# Hovedkort.net
KiCad netlist of a schematic drawn in Altium Designer
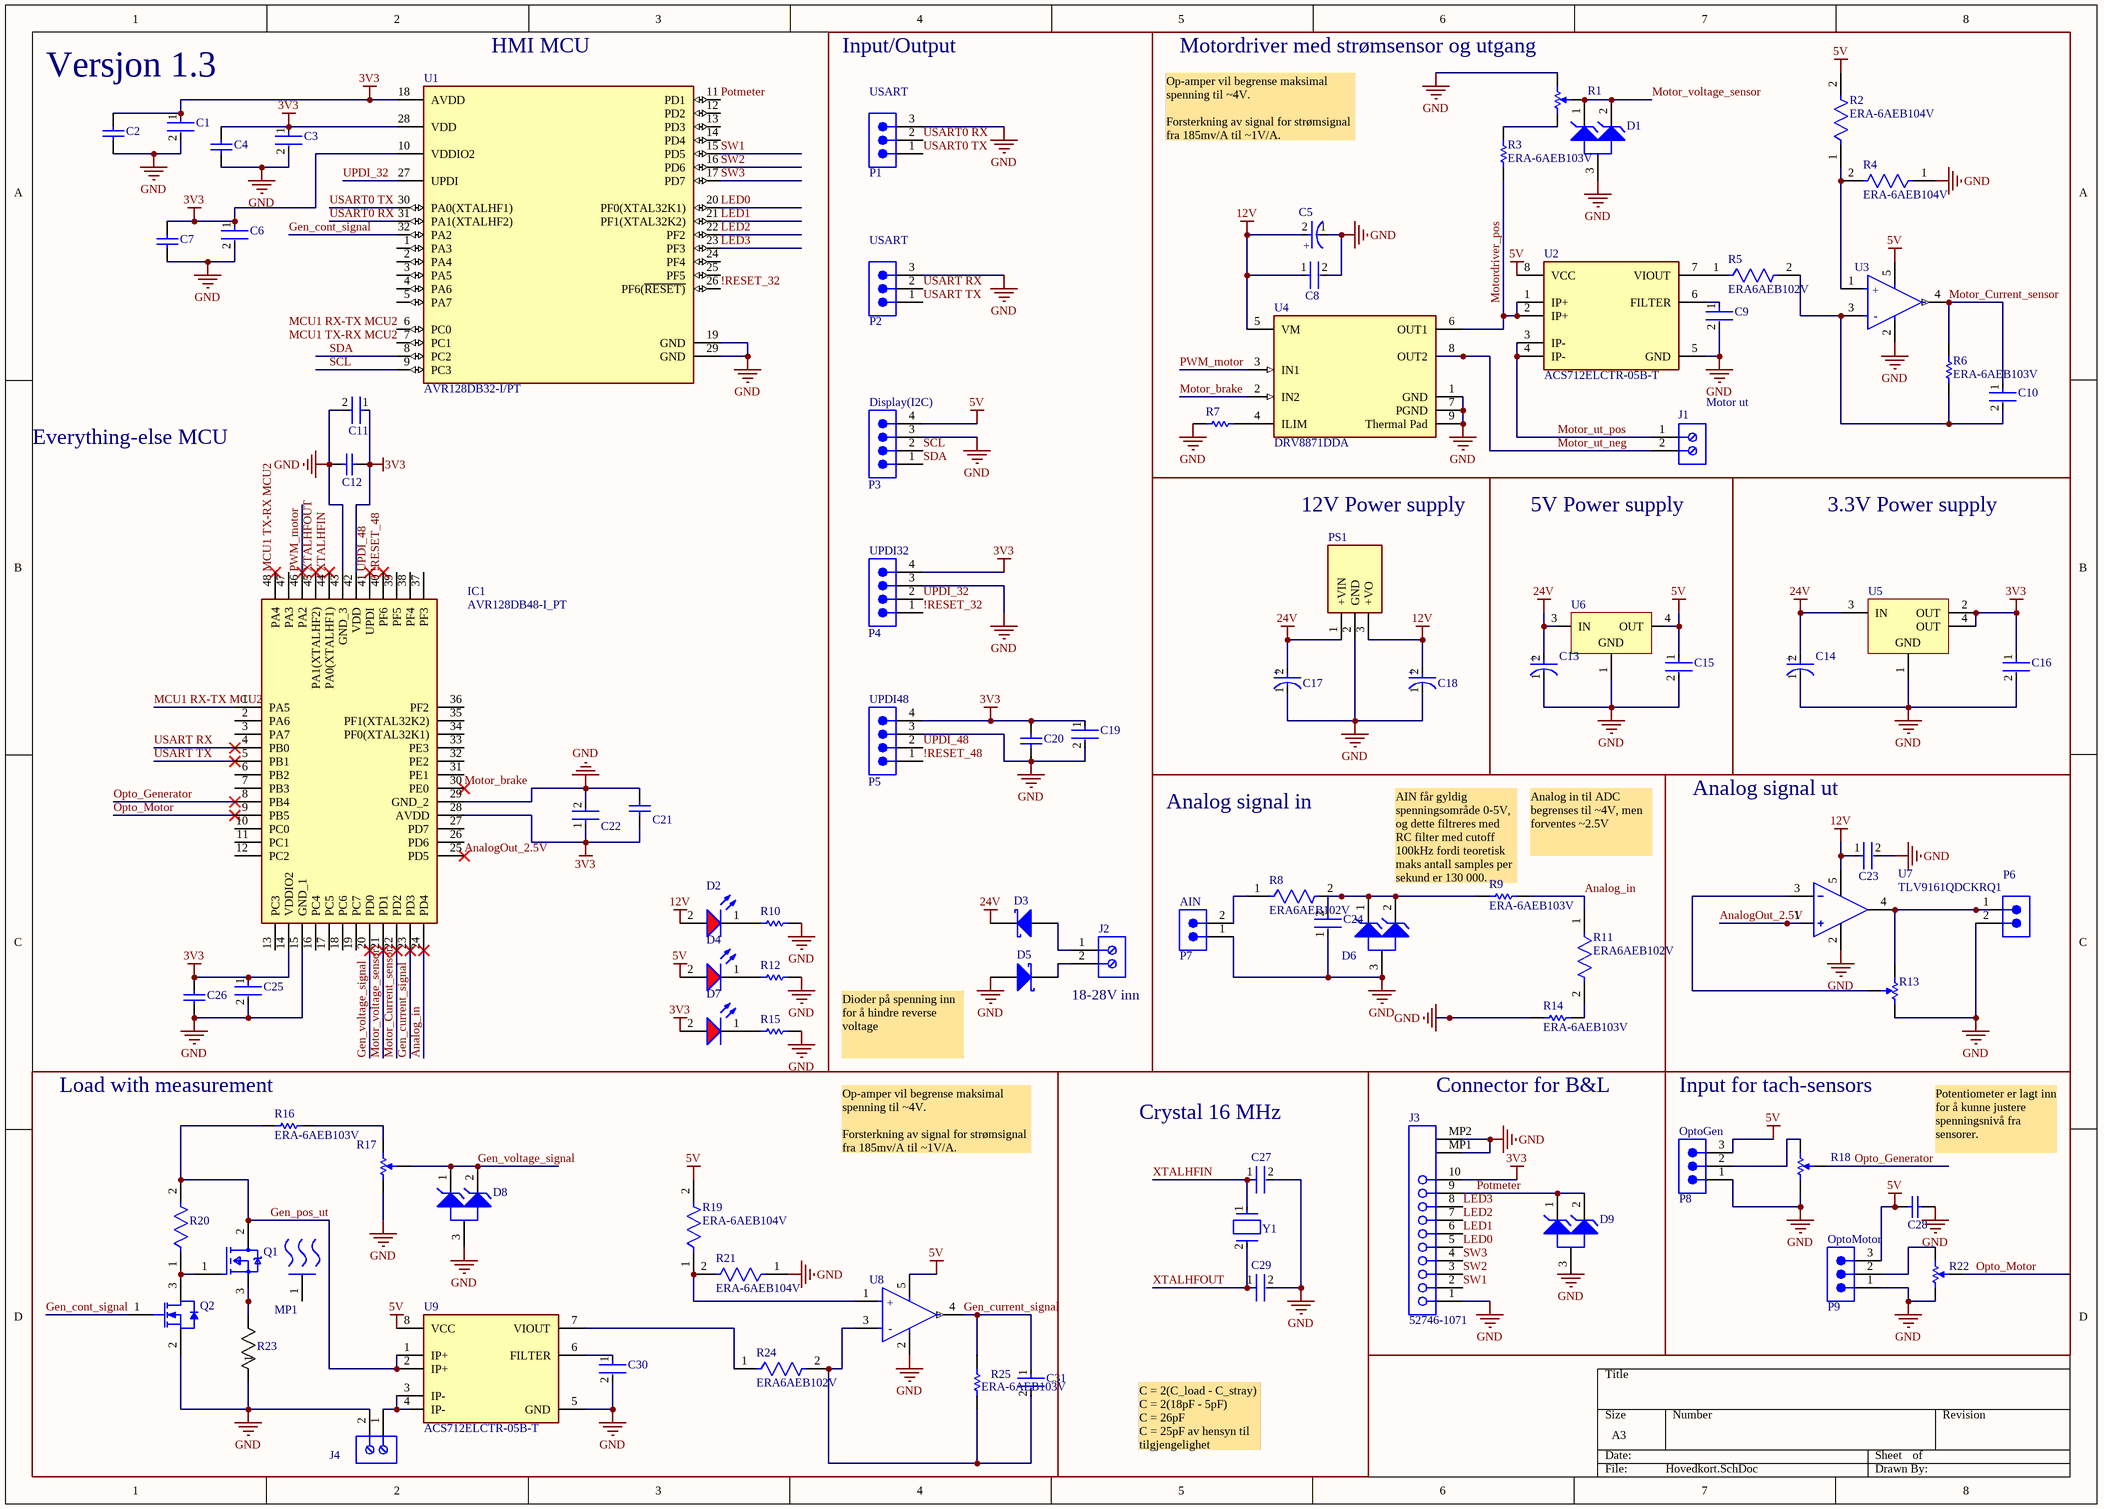
[diagram p0: Hovedkort.SchDoc]

(export (version "E")
  (design (tool "Eeschema 10.0.6"))
  (components
    (comp (ref "C1")
      (value "08055C104KAT2A")
      (footprint "FP-0805-L_2_01_0_2-W_1_25-IPC_C")
      (description "General Purpose Ceramic Capacitor, 0805, 100nF, 10%, X7R, 0.15, 50V")
      (fields (field (name "TOLERANCE") "10%") (field (name "VOLTAGE") "50V"))
      (libsource (lib "Altium Content Vault") (part "02cd4be3c70576c341d710602a673aa"))
    )
    (comp (ref "C2")
      (value "C0805C103K5RACTU")
      (footprint "CAPC2013X88X50LL20T25")
      (fields (field (name "MANUFACTURER") "Kemet"))
      (libsource (lib "Altium Content Vault") (part "CAP"))
    )
    (comp (ref "C3")
      (value "08055C104KAT2A")
      (footprint "FP-0805-L_2_01_0_2-W_1_25-IPC_C")
      (description "General Purpose Ceramic Capacitor, 0805, 100nF, 10%, X7R, 0.15, 50V")
      (fields (field (name "TOLERANCE") "10%") (field (name "VOLTAGE") "50V"))
      (libsource (lib "Altium Content Vault") (part "02cd4be3c70576c341d710602a673aa"))
    )
    (comp (ref "C4")
      (value "C0805C103K5RACTU")
      (footprint "CAPC2013X88X50LL20T25")
      (fields (field (name "MANUFACTURER") "Kemet"))
      (libsource (lib "Altium Content Vault") (part "CAP"))
    )
    (comp (ref "C5")
      (value "EEEFK1V220R")
      (footprint "FP-FKC-MFG")
      (description "CAP ALUM 22UF 20% 35V SMD")
      (fields (field (name "VOLTAGE") "35V") (field (name "TOLERANCE") "20%"))
      (libsource (lib "Altium Content Vault") (part "a00bbbee19879c290e62620ae7e47b1"))
    )
    (comp (ref "C6")
      (value "08055C104KAT2A")
      (footprint "FP-0805-L_2_01_0_2-W_1_25-IPC_C")
      (description "General Purpose Ceramic Capacitor, 0805, 100nF, 10%, X7R, 0.15, 50V")
      (fields (field (name "TOLERANCE") "10%") (field (name "VOLTAGE") "50V"))
      (libsource (lib "Altium Content Vault") (part "02cd4be3c70576c341d710602a673aa"))
    )
    (comp (ref "C7")
      (value "C0805C103K5RACTU")
      (footprint "CAPC2013X88X50LL20T25")
      (fields (field (name "MANUFACTURER") "Kemet"))
      (libsource (lib "Altium Content Vault") (part "CAP"))
    )
    (comp (ref "C8")
      (value "08055C104KAT2A")
      (footprint "FP-0805-L_2_01_0_2-W_1_25-IPC_C")
      (description "General Purpose Ceramic Capacitor, 0805, 100nF, 10%, X7R, 0.15, 50V")
      (fields (field (name "TOLERANCE") "10%") (field (name "VOLTAGE") "50V"))
      (libsource (lib "Altium Content Vault") (part "02cd4be3c70576c341d710602a673aa"))
    )
    (comp (ref "C9")
      (value "08055C104KAT2A")
      (footprint "FP-0805-L_2_01_0_2-W_1_25-IPC_C")
      (description "General Purpose Ceramic Capacitor, 0805, 100nF, 10%, X7R, 0.15, 50V")
      (fields (field (name "TOLERANCE") "10%") (field (name "VOLTAGE") "50V"))
      (libsource (lib "Altium Content Vault") (part "02cd4be3c70576c341d710602a673aa"))
    )
    (comp (ref "C10")
      (value "C0805C102J1GACTU")
      (footprint "FP-C0805C-DN-MFG")
      (description "CAP CER 1000PF 100V C0G/NP0 0805")
      (fields (field (name "MANUFACTURER") "KEMET") (field (name "TOLERANCE") "0.05"))
      (libsource (lib "Altium Content Vault") (part "b4654b650e69147ec39a6b967a45e02"))
    )
    (comp (ref "C11")
      (value "08055C104KAT2A")
      (footprint "FP-0805-L_2_01_0_2-W_1_25-IPC_C")
      (description "General Purpose Ceramic Capacitor, 0805, 100nF, 10%, X7R, 0.15, 50V")
      (fields (field (name "TOLERANCE") "10%") (field (name "VOLTAGE") "50V"))
      (libsource (lib "Altium Content Vault") (part "02cd4be3c70576c341d710602a673aa"))
    )
    (comp (ref "C12")
      (value "C0805C103K5RACTU")
      (footprint "CAPC2013X88X50LL20T25")
      (fields (field (name "MANUFACTURER") "Kemet"))
      (libsource (lib "Altium Content Vault") (part "CAP"))
    )
    (comp (ref "C13")
      (value "EEE-FK1H100UR")
      (footprint "FP-FKC-MFG")
      (description "CAP ALUM 10UF 20% 50V SMD")
      (fields (field (name "TOLERANCE") "20%") (field (name "VOLTAGE") "50V"))
      (libsource (lib "Altium Content Vault") (part "a00bbbee19879c290e62620ae7e47b1"))
    )
    (comp (ref "C14")
      (value "EEE-FK1H100UR")
      (footprint "FP-FKC-MFG")
      (description "CAP ALUM 10UF 20% 50V SMD")
      (fields (field (name "TOLERANCE") "20%") (field (name "VOLTAGE") "50V"))
      (libsource (lib "Altium Content Vault") (part "a00bbbee19879c290e62620ae7e47b1"))
    )
    (comp (ref "C15")
      (value "C0805C106K8PACTU")
      (footprint "FP-C0805C-DG-MFG")
      (description "CAP CER 10UF 10V X5R 0805")
      (fields (field (name "TOLERANCE") "10%") (field (name "MANUFACTURER") "Kemet"))
      (libsource (lib "Altium Content Vault") (part "11868f565c42a9108669ba33697ecf6"))
    )
    (comp (ref "C16")
      (value "C0805C106K8PACTU")
      (footprint "FP-C0805C-DG-MFG")
      (description "CAP CER 10UF 10V X5R 0805")
      (fields (field (name "TOLERANCE") "10%") (field (name "MANUFACTURER") "Kemet"))
      (libsource (lib "Altium Content Vault") (part "11868f565c42a9108669ba33697ecf6"))
    )
    (comp (ref "C17")
      (value "EEEFK1V220R")
      (footprint "FP-FKC-MFG")
      (description "CAP ALUM 22UF 20% 35V SMD")
      (fields (field (name "VOLTAGE") "35V") (field (name "TOLERANCE") "20%"))
      (libsource (lib "Altium Content Vault") (part "a00bbbee19879c290e62620ae7e47b1"))
    )
    (comp (ref "C18")
      (value "EEEFK1V220R")
      (footprint "FP-FKC-MFG")
      (description "CAP ALUM 22UF 20% 35V SMD")
      (fields (field (name "VOLTAGE") "35V") (field (name "TOLERANCE") "20%"))
      (libsource (lib "Altium Content Vault") (part "a00bbbee19879c290e62620ae7e47b1"))
    )
    (comp (ref "C19")
      (value "08055C104KAT2A")
      (footprint "FP-0805-L_2_01_0_2-W_1_25-IPC_C")
      (description "General Purpose Ceramic Capacitor, 0805, 100nF, 10%, X7R, 0.15, 50V")
      (fields (field (name "TOLERANCE") "10%") (field (name "VOLTAGE") "50V"))
      (libsource (lib "Altium Content Vault") (part "02cd4be3c70576c341d710602a673aa"))
    )
    (comp (ref "C20")
      (value "C0805C103K5RACTU")
      (footprint "CAPC2013X88X50LL20T25")
      (fields (field (name "MANUFACTURER") "Kemet"))
      (libsource (lib "Altium Content Vault") (part "CAP"))
    )
    (comp (ref "C21")
      (value "C0805C103K5RACTU")
      (footprint "CAPC2013X88X50LL20T25")
      (fields (field (name "MANUFACTURER") "Kemet"))
      (libsource (lib "Altium Content Vault") (part "CAP"))
    )
    (comp (ref "C22")
      (value "08055C104KAT2A")
      (footprint "FP-0805-L_2_01_0_2-W_1_25-IPC_C")
      (description "General Purpose Ceramic Capacitor, 0805, 100nF, 10%, X7R, 0.15, 50V")
      (fields (field (name "TOLERANCE") "10%") (field (name "VOLTAGE") "50V"))
      (libsource (lib "Altium Content Vault") (part "02cd4be3c70576c341d710602a673aa"))
    )
    (comp (ref "C23")
      (value "08055C104KAT2A")
      (footprint "FP-0805-L_2_01_0_2-W_1_25-IPC_C")
      (description "General Purpose Ceramic Capacitor, 0805, 100nF, 10%, X7R, 0.15, 50V")
      (fields (field (name "TOLERANCE") "10%") (field (name "VOLTAGE") "50V"))
      (libsource (lib "Altium Content Vault") (part "02cd4be3c70576c341d710602a673aa"))
    )
    (comp (ref "C24")
      (value "GRM2165C2A162JA01D")
      (footprint "FP-GRM216-0_1-IPC_A")
      (description "Chip Multilayer Ceramic Capacitors for General Purpose, 0805, 1600pF, C0G, 30ppm/°C, 5%, 100V")
      (fields (field (name "TOLERANCE") "5%"))
      (libsource (lib "Altium Content Vault") (part "236180d848d6139a670b325ea6854c9"))
    )
    (comp (ref "C25")
      (value "08055C104KAT2A")
      (footprint "FP-0805-L_2_01_0_2-W_1_25-IPC_C")
      (description "General Purpose Ceramic Capacitor, 0805, 100nF, 10%, X7R, 0.15, 50V")
      (fields (field (name "TOLERANCE") "10%") (field (name "VOLTAGE") "50V"))
      (libsource (lib "Altium Content Vault") (part "02cd4be3c70576c341d710602a673aa"))
    )
    (comp (ref "C26")
      (value "C0805C103K5RACTU")
      (footprint "CAPC2013X88X50LL20T25")
      (fields (field (name "MANUFACTURER") "Kemet"))
      (libsource (lib "Altium Content Vault") (part "CAP"))
    )
    (comp (ref "C27")
      (value "C0805C103J3GACTU")
      (footprint "FP-C0805C-DN-MFG")
      (description "CAP CER 10000PF 25V 5% NP0 0805")
      (fields
        (field (name "OCTOPART") "https://octopart.com/c0805c103j3gactu-kemet-12563663")
        (field (name "TOLERANCE") "0.05")
      )
      (libsource (lib "Altium Content Vault") (part "b4654b650e69147ec39a6b967a45e02"))
    )
    (comp (ref "C28")
      (value "C0805C103K5RACTU")
      (footprint "CAPC2013X88X50LL20T25")
      (fields (field (name "MANUFACTURER") "Kemet"))
      (libsource (lib "Altium Content Vault") (part "CAP"))
    )
    (comp (ref "C29")
      (value "C0805C103J3GACTU")
      (footprint "FP-C0805C-DN-MFG")
      (description "CAP CER 10000PF 25V 5% NP0 0805")
      (fields
        (field (name "OCTOPART") "https://octopart.com/c0805c103j3gactu-kemet-12563663")
        (field (name "TOLERANCE") "0.05")
      )
      (libsource (lib "Altium Content Vault") (part "b4654b650e69147ec39a6b967a45e02"))
    )
    (comp (ref "C30")
      (value "08055C104KAT2A")
      (footprint "FP-0805-L_2_01_0_2-W_1_25-IPC_C")
      (description "General Purpose Ceramic Capacitor, 0805, 100nF, 10%, X7R, 0.15, 50V")
      (fields (field (name "TOLERANCE") "10%") (field (name "VOLTAGE") "50V"))
      (libsource (lib "Altium Content Vault") (part "02cd4be3c70576c341d710602a673aa"))
    )
    (comp (ref "C31")
      (value "C0805C102J1GACTU")
      (footprint "FP-C0805C-DN-MFG")
      (description "CAP CER 1000PF 100V C0G/NP0 0805")
      (fields (field (name "MANUFACTURER") "KEMET") (field (name "TOLERANCE") "0.05"))
      (libsource (lib "Altium Content Vault") (part "b4654b650e69147ec39a6b967a45e02"))
    )
    (comp (ref "D1")
      (value "MMBZ6V2ALT1G")
      (footprint "ONSC-SOT-23-3-318-08_V")
      (fields (field (name "MANUFACTURER") "On Semiconductor"))
      (libsource (lib "Altium Content Vault") (part "ONSC-K1K2A3-3"))
    )
    (comp (ref "D2")
      (value "150080SS75000")
      (footprint "WL-SMCW_0805_150080xx75000")
      (libsource (lib "Altium Content Vault") (part "LED_Red_2A-1K"))
    )
    (comp (ref "D3")
      (value "STPS2H100A")
      (footprint "STM-SMA-2_V")
      (description "Power Schottky Rectifier, 2 A, 100 V, 2-Pin SMD (SMA), RoHS, Tape and Reel")
      (fields (field (name "MANUFACTURER") "STMicroelectronics"))
      (libsource (lib "Altium Content Vault") (part "DSKY-AK-2"))
    )
    (comp (ref "D4")
      (value "150080SS75000")
      (footprint "WL-SMCW_0805_150080xx75000")
      (libsource (lib "Altium Content Vault") (part "LED_Red_2A-1K"))
    )
    (comp (ref "D5")
      (value "STPS2H100A")
      (footprint "STM-SMA-2_V")
      (description "Power Schottky Rectifier, 2 A, 100 V, 2-Pin SMD (SMA), RoHS, Tape and Reel")
      (fields (field (name "MANUFACTURER") "STMicroelectronics"))
      (libsource (lib "Altium Content Vault") (part "DSKY-AK-2"))
    )
    (comp (ref "D6")
      (value "ESD7L5.0DT5G")
      (footprint "ONSC-SOT-723-3-631AA-01_V")
      (fields (field (name "MANUFACTURER") "On Semiconductor"))
      (libsource (lib "Altium Content Vault") (part "ONSC-K1K2A3-3"))
    )
    (comp (ref "D7")
      (value "150080SS75000")
      (footprint "WL-SMCW_0805_150080xx75000")
      (libsource (lib "Altium Content Vault") (part "LED_Red_2A-1K"))
    )
    (comp (ref "D8")
      (value "MMBZ6V2ALT1G")
      (footprint "ONSC-SOT-23-3-318-08_V")
      (fields (field (name "MANUFACTURER") "On Semiconductor"))
      (libsource (lib "Altium Content Vault") (part "ONSC-K1K2A3-3"))
    )
    (comp (ref "D9")
      (value "SZMMBZ27VAWT1G")
      (footprint "ONSC-SC-70-3-419-04_V")
      (fields (field (name "MANUFACTURER") "On Semiconductor"))
      (libsource (lib "Altium Content Vault") (part "ONSC-K1K2A3-3"))
    )
    (comp (ref "IC1")
      (value "AVR128DB48-I_PT")
      (footprint "QFP50P900X900X120-48N")
      (description "Integrated Circuit")
      (fields
        (field (name "MANUFACTURER_PART_NUMBER") "AVR128DB48-I/PT")
        (field (name "MOUSER PART NUMBER") "579-AVR128DB48-I/PT")
      )
      (libsource (lib "AVR128DB48-iPTv3") (part "AVR128DB48-I_PT"))
    )
    (comp (ref "J1")
      (value "691103110002")
      (footprint "691103110002")
      (fields (field (name "VOLTAGE") "125V"))
      (libsource (lib "Altium Content Vault") (part "TBL - 1R - 02P - Screw"))
    )
    (comp (ref "J2")
      (value "691103110002")
      (footprint "691103110002")
      (fields (field (name "VOLTAGE") "125V"))
      (libsource (lib "Altium Content Vault") (part "TBL - 1R - 02P - Screw"))
    )
    (comp (ref "J3")
      (value "52746-1071")
      (footprint "MOLX-52746-1071")
      (fields (field (name "MANUFACTURER") "Molex"))
      (libsource (lib "Altium Content Vault") (part "MOLX-52746-1071"))
    )
    (comp (ref "J4")
      (value "691103110002")
      (footprint "691103110002")
      (fields (field (name "VOLTAGE") "125V"))
      (libsource (lib "Altium Content Vault") (part "TBL - 1R - 02P - Screw"))
    )
    (comp (ref "MP1")
      (value "FA-T220-25E")
      (footprint "FP-FA-T220-25E-MFG")
      (description "HEATSINK TO-218,TO-220,TO-247")
      (libsource (lib "Altium Content Vault") (part "6f3fc7de95079af55ca25afa00d65c5"))
    )
    (comp (ref "P1")
      (value "61300311121")
      (footprint "61300311121")
      (libsource (lib "Altium Content Vault") (part "Header_Male_1R_03P"))
    )
    (comp (ref "P2")
      (value "61300311121")
      (footprint "61300311121")
      (libsource (lib "Altium Content Vault") (part "Header_Male_1R_03P"))
    )
    (comp (ref "P3")
      (value "61300411121")
      (footprint "61300411121")
      (libsource (lib "Altium Content Vault") (part "Header_Male_1R_04P"))
    )
    (comp (ref "P4")
      (value "61300411121")
      (footprint "61300411121")
      (libsource (lib "Altium Content Vault") (part "Header_Male_1R_04P"))
    )
    (comp (ref "P5")
      (value "61300411121")
      (footprint "61300411121")
      (libsource (lib "Altium Content Vault") (part "Header_Male_1R_04P"))
    )
    (comp (ref "P6")
      (value "61300211121")
      (footprint "61300211121")
      (libsource (lib "Altium Content Vault") (part "Header_Male_1R_02P"))
    )
    (comp (ref "P7")
      (value "61300211121")
      (footprint "61300211121")
      (libsource (lib "Altium Content Vault") (part "Header_Male_1R_02P"))
    )
    (comp (ref "P8")
      (value "61300311121")
      (footprint "61300311121")
      (libsource (lib "Altium Content Vault") (part "Header_Male_1R_03P"))
    )
    (comp (ref "P9")
      (value "61300311121")
      (footprint "61300311121")
      (libsource (lib "Altium Content Vault") (part "Header_Male_1R_03P"))
    )
    (comp (ref "PS1")
      (value "P7812-2000R-S")
      (footprint "P78032000RS")
      (description "Power Supply")
      (libsource (lib "P7803-2000R-S") (part "P7803-2000R-S"))
    )
    (comp (ref "Q1")
      (value "IRFZ44VPBF")
      (footprint "FP-PG-TO220-3-MFG")
      (description "MOSFET N-CH 60V 55A TO220AB")
      (libsource (lib "Altium Content Vault") (part "8b62d417cbef8344eebe0bde0c45977"))
    )
    (comp (ref "Q2")
      (value "BSH103,215")
      (footprint "NXP-SOT23_N")
      (description "N-Channel Enhancement Mode MOS Transistor, 30 V, 0.85 A, 3-Pin SOT23, Tape and Reel")
      (fields (field (name "MANUFACTURER") "NXP Semiconductors"))
      (libsource (lib "Altium Content Vault") (part "NXP-NMOS-GSD-3_B"))
    )
    (comp (ref "R1")
      (value "TC33X-2-103E")
      (footprint "BOUR-TC33X-2_V")
      (description "Trimming Potentiometer, 10000 Ohm, -40 to 100 degC, 3-Pin SMD, RoHS, Tape and Reel")
      (fields (field (name "TOLERANCE") "25%") (field (name "MANUFACTURER") "Bourns"))
      (libsource (lib "Altium Content Vault") (part "RES-ADJ-3_A"))
    )
    (comp (ref "R2")
      (value "ERA-6AEB104V")
      (footprint "FP-ERA6A-IPC_B")
      (description "RES 100K OHM 0.1% 1/8W 0805")
      (fields (field (name "TOLERANCE") "0.1%"))
      (libsource (lib "Altium Content Vault") (part "1029c3af85768c4190bb7ad29bc67b5"))
    )
    (comp (ref "R3")
      (value "ERA-6AEB103V")
      (footprint "RESC2013X60X40LL20T25_A")
      (fields (field (name "TOLERANCE") "0.1%") (field (name "MANUFACTURER") "Panasonic"))
      (libsource (lib "Altium Content Vault") (part "RES-2"))
    )
    (comp (ref "R4")
      (value "ERA-6AEB104V")
      (footprint "FP-ERA6A-IPC_B")
      (description "RES 100K OHM 0.1% 1/8W 0805")
      (fields (field (name "TOLERANCE") "0.1%"))
      (libsource (lib "Altium Content Vault") (part "1029c3af85768c4190bb7ad29bc67b5"))
    )
    (comp (ref "R5")
      (value "ERA6AEB102V")
      (footprint "FP-ERA6A-IPC_C")
      (description "RES 1K OHM 0.1% 1/8W 0805")
      (fields (field (name "TOLERANCE") "0.1%"))
      (libsource (lib "Altium Content Vault") (part "1029c3af85768c4190bb7ad29bc67b5"))
    )
    (comp (ref "R6")
      (value "ERA-6AEB103V")
      (footprint "RESC2013X60X40LL20T25_A")
      (fields (field (name "TOLERANCE") "0.1%") (field (name "MANUFACTURER") "Panasonic"))
      (libsource (lib "Altium Content Vault") (part "RES-2"))
    )
    (comp (ref "R7")
      (value "ERJ-6GEYJ303V")
      (footprint "RESC2013X70X40NL20T20")
      (fields (field (name "MANUFACTURER") "Panasonic"))
      (libsource (lib "Altium Content Vault") (part "RES"))
    )
    (comp (ref "R8")
      (value "ERA6AEB102V")
      (footprint "FP-ERA6A-IPC_C")
      (description "RES 1K OHM 0.1% 1/8W 0805")
      (fields (field (name "TOLERANCE") "0.1%"))
      (libsource (lib "Altium Content Vault") (part "1029c3af85768c4190bb7ad29bc67b5"))
    )
    (comp (ref "R9")
      (value "ERA-6AEB103V")
      (footprint "RESC2013X60X40LL20T25_A")
      (fields (field (name "TOLERANCE") "0.1%") (field (name "MANUFACTURER") "Panasonic"))
      (libsource (lib "Altium Content Vault") (part "RES-2"))
    )
    (comp (ref "R10")
      (value "ERJ-6GEYJ511V")
      (footprint "RESC2013X70X40ML20T20")
      (fields (field (name "MANUFACTURER") "Panasonic"))
      (libsource (lib "Altium Content Vault") (part "RES"))
    )
    (comp (ref "R11")
      (value "ERA6AEB102V")
      (footprint "FP-ERA6A-IPC_C")
      (description "RES 1K OHM 0.1% 1/8W 0805")
      (fields (field (name "TOLERANCE") "0.1%"))
      (libsource (lib "Altium Content Vault") (part "1029c3af85768c4190bb7ad29bc67b5"))
    )
    (comp (ref "R12")
      (value "ERA6AEB1400V")
      (footprint "RESC2013X60X40NL20T25")
      (fields (field (name "MANUFACTURER") "Panasonic"))
      (libsource (lib "Altium Content Vault") (part "RES"))
    )
    (comp (ref "R13")
      (value "TC33X-2-103E")
      (footprint "BOUR-TC33X-2_V")
      (description "Trimming Potentiometer, 10000 Ohm, -40 to 100 degC, 3-Pin SMD, RoHS, Tape and Reel")
      (fields (field (name "TOLERANCE") "25%") (field (name "MANUFACTURER") "Bourns"))
      (libsource (lib "Altium Content Vault") (part "RES-ADJ-3_A"))
    )
    (comp (ref "R14")
      (value "ERA-6AEB103V")
      (footprint "RESC2013X60X40LL20T25_A")
      (fields (field (name "TOLERANCE") "0.1%") (field (name "MANUFACTURER") "Panasonic"))
      (libsource (lib "Altium Content Vault") (part "RES-2"))
    )
    (comp (ref "R15")
      (value "ERJ6ENF56R0V")
      (footprint "RESC2013X70X40NL20T20")
      (fields (field (name "MANUFACTURER") "Panasonic"))
      (libsource (lib "Altium Content Vault") (part "RES"))
    )
    (comp (ref "R16")
      (value "ERA-6AEB103V")
      (footprint "RESC2013X60X40LL20T25_A")
      (fields (field (name "TOLERANCE") "0.1%") (field (name "MANUFACTURER") "Panasonic"))
      (libsource (lib "Altium Content Vault") (part "RES-2"))
    )
    (comp (ref "R17")
      (value "TC33X-2-103E")
      (footprint "BOUR-TC33X-2_V")
      (description "Trimming Potentiometer, 10000 Ohm, -40 to 100 degC, 3-Pin SMD, RoHS, Tape and Reel")
      (fields (field (name "TOLERANCE") "25%") (field (name "MANUFACTURER") "Bourns"))
      (libsource (lib "") (part "RES-ADJ-3_A_1"))
    )
    (comp (ref "R18")
      (value "TC33X-2-103E")
      (footprint "BOUR-TC33X-2_V")
      (description "Trimming Potentiometer, 10000 Ohm, -40 to 100 degC, 3-Pin SMD, RoHS, Tape and Reel")
      (fields (field (name "TOLERANCE") "25%") (field (name "MANUFACTURER") "Bourns"))
      (libsource (lib "Altium Content Vault") (part "RES-ADJ-3_A"))
    )
    (comp (ref "R19")
      (value "ERA-6AEB104V")
      (footprint "FP-ERA6A-IPC_B")
      (description "RES 100K OHM 0.1% 1/8W 0805")
      (fields (field (name "TOLERANCE") "0.1%"))
      (libsource (lib "Altium Content Vault") (part "1029c3af85768c4190bb7ad29bc67b5"))
    )
    (comp (ref "R20")
      (value "CRCW080510K0FKEA")
      (footprint "FP-CRCW0805-e3-IPC_A")
      (description "RES Thick Film, 10kΩ, 1%, 0.125W, 100ppm/°C, 0805")
      (fields (field (name "TOLERANCE") "1%"))
      (libsource (lib "Altium Content Vault") (part "1029c3af85768c4190bb7ad29bc67b5"))
    )
    (comp (ref "R21")
      (value "ERA-6AEB104V")
      (footprint "FP-ERA6A-IPC_B")
      (description "RES 100K OHM 0.1% 1/8W 0805")
      (fields (field (name "TOLERANCE") "0.1%"))
      (libsource (lib "Altium Content Vault") (part "1029c3af85768c4190bb7ad29bc67b5"))
    )
    (comp (ref "R22")
      (value "TC33X-2-103E")
      (footprint "BOUR-TC33X-2_V")
      (description "Trimming Potentiometer, 10000 Ohm, -40 to 100 degC, 3-Pin SMD, RoHS, Tape and Reel")
      (fields (field (name "TOLERANCE") "25%") (field (name "MANUFACTURER") "Bourns"))
      (libsource (lib "Altium Content Vault") (part "RES-ADJ-3_A"))
    )
    (comp (ref "R23")
      (value "AC05000001008JAC00")
      (footprint "RES_AC05_VIS")
      (fields (field (name "TOLERANCE") "5%"))
      (libsource (lib "Altium Content Vault") (part "AC05000001008JAC00"))
    )
    (comp (ref "R24")
      (value "ERA6AEB102V")
      (footprint "FP-ERA6A-IPC_C")
      (description "RES 1K OHM 0.1% 1/8W 0805")
      (fields (field (name "TOLERANCE") "0.1%"))
      (libsource (lib "Altium Content Vault") (part "1029c3af85768c4190bb7ad29bc67b5"))
    )
    (comp (ref "R25")
      (value "ERA-6AEB103V")
      (footprint "RESC2013X60X40LL20T25_A")
      (fields (field (name "TOLERANCE") "0.1%") (field (name "MANUFACTURER") "Panasonic"))
      (libsource (lib "Altium Content Vault") (part "RES-2"))
    )
    (comp (ref "U1")
      (value "AVR128DB32-I/PT")
      (footprint "FP-C04-074-PT-MFG")
      (description "AVR128DB32-I/PT 8-bit AVR MCU, 128 KB, 16384 Bytes, 24 MHz, 1.8 to 5.5V, TQFP-32, RoHS")
      (libsource (lib "Altium Content Vault") (part "862fc9fb584fc62f03dcc95c93de750"))
    )
    (comp (ref "U2")
      (value "ACS712ELCTR-05B-T")
      (footprint "FP-LC-8-IPC_A")
      (description "SENSOR CURRENT HALL 5A AC/DC")
      (fields (field (name "VOLTAGE") "5V"))
      (libsource (lib "Altium Content Vault") (part "160a4736de78720bdb7fdad13a6f0ac"))
    )
    (comp (ref "U3")
      (value "LM321LVIDCKR")
      (footprint "FP-DCK0005A-IPC_B")
      (description "IC OPAMP GP 1 CIRCUIT SC70-5")
      (libsource (lib "Altium Content Vault") (part "471d8b929410cd356ad4b122f572ce5"))
    )
    (comp (ref "U4")
      (value "DRV8871DDA")
      (footprint "FP-DDA0008E-IPC_B")
      (description "IC MOTOR DRVR UNIPLR 8SO PWRPAD")
      (libsource (lib "Altium Content Vault") (part "e376993584eeff15c1aa71204cd03ad"))
    )
    (comp (ref "U5")
      (value "LD1086D2M33TR")
      (footprint "D2PAK_A_L")
      (description "1.5A, Low Drop Positive Voltage Regulator, 3.3V, 4-Pin D2PAK/A, Tape and Reel")
      (libsource (lib "Altium Content Vault") (part "PM-REG-LD1085-SOT4"))
    )
    (comp (ref "U6")
      (value "LD1086D2T50TR")
      (footprint "TO-263_N")
      (description "1.5A, Low Drop Positive Voltage Regulator, 5.0V, 3-Pin D2PAK, Tape and Reel")
      (libsource (lib "Altium Content Vault") (part "PM-REG-LD1085-SOT3"))
    )
    (comp (ref "U7")
      (value "TLV9161QDCKRQ1")
      (footprint "FP-DCK0005A-MFG")
      (libsource (lib "Altium Content Vault") (part "bd543cf93bb0a89a308ea7e9b7b5175"))
    )
    (comp (ref "U8")
      (value "LM321LVIDCKR")
      (footprint "FP-DCK0005A-IPC_B")
      (description "IC OPAMP GP 1 CIRCUIT SC70-5")
      (libsource (lib "Altium Content Vault") (part "471d8b929410cd356ad4b122f572ce5"))
    )
    (comp (ref "U9")
      (value "ACS712ELCTR-05B-T")
      (footprint "FP-LC-8-IPC_A")
      (description "SENSOR CURRENT HALL 5A AC/DC")
      (fields (field (name "VOLTAGE") "5V"))
      (libsource (lib "Altium Content Vault") (part "160a4736de78720bdb7fdad13a6f0ac"))
    )
    (comp (ref "Y1")
      (value "ABM3-16.000MHZ-B2-T")
      (footprint "FP-ABM3-MFG")
      (description "Crystal 16MHz ±20ppm 18pF SMD-2 5mm x 3.2mm")
      (fields (field (name "TOLERANCE") "20ppm"))
      (libsource (lib "Altium Content Vault") (part "c23a69dc6c9e2f18f2079038eb95dd1"))
    )
  )
  (nets
    (net (code "1") (name "/!RESET_32") (class "Default")
      (node (ref "P4") (pin "1") (pinfunction "1_1") (pintype "passive"))
      (node (ref "U1") (pin "26") (pinfunction "PF6(~{RESET)}_26") (pintype "bidirectional"))
    )
    (net (code "2") (name "/!RESET_48") (class "Default")
      (node (ref "IC1") (pin "40") (pinfunction "PF6_40") (pintype "passive"))
      (node (ref "P5") (pin "1") (pinfunction "1_1") (pintype "passive"))
    )
    (net (code "3") (name "/AnalogOut_2.5V") (class "Default")
      (node (ref "IC1") (pin "25") (pinfunction "PD5_25") (pintype "passive"))
      (node (ref "U7") (pin "1") (pinfunction "IN+_1") (pintype "tri_state"))
    )
    (net (code "4") (name "/Analog_in") (class "Default")
      (node (ref "IC1") (pin "24") (pinfunction "PD4_24") (pintype "passive"))
      (node (ref "R11") (pin "1") (pinfunction "1_1") (pintype "passive"))
      (node (ref "R9") (pin "1") (pinfunction "1_1") (pintype "passive"))
    )
    (net (code "5") (name "/Gen_cont_signal") (class "Default")
      (node (ref "Q2") (pin "1") (pinfunction "G_1") (pintype "passive"))
      (node (ref "U1") (pin "32") (pinfunction "PA2_32") (pintype "bidirectional"))
    )
    (net (code "6") (name "/Gen_current_signal") (class "Default")
      (node (ref "C31") (pin "1") (pinfunction "1_1") (pintype "passive"))
      (node (ref "IC1") (pin "23") (pinfunction "PD3_23") (pintype "passive"))
      (node (ref "R25") (pin "2") (pinfunction "2_2") (pintype "passive"))
      (node (ref "U8") (pin "4") (pinfunction "OUT_4") (pintype "output"))
    )
    (net (code "7") (name "/Gen_pos_ut") (class "Default")
      (node (ref "Q1") (pin "2") (pinfunction "DRAIN_2") (pintype "passive"))
      (node (ref "R16") (pin "2") (pinfunction "2_2") (pintype "passive"))
      (node (ref "R20") (pin "2") (pinfunction "2_2") (pintype "passive"))
      (node (ref "U9") (pin "1") (pinfunction "IP+_1") (pintype "passive"))
      (node (ref "U9") (pin "2") (pinfunction "IP+_2") (pintype "passive"))
    )
    (net (code "8") (name "/Gen_voltage_signal") (class "Default")
      (node (ref "D8") (pin "1") (pinfunction "K1_1") (pintype "passive"))
      (node (ref "D8") (pin "2") (pinfunction "K2_2") (pintype "passive"))
      (node (ref "IC1") (pin "20") (pinfunction "PD0_20") (pintype "passive"))
      (node (ref "R17") (pin "2") (pinfunction "2_2") (pintype "passive"))
    )
    (net (code "9") (name "/LED0") (class "Default")
      (node (ref "J3") (pin "5") (pinfunction "5_5") (pintype "passive"))
      (node (ref "U1") (pin "20") (pinfunction "PF0(XTAL32K1)_20") (pintype "bidirectional"))
    )
    (net (code "10") (name "/LED1") (class "Default")
      (node (ref "J3") (pin "6") (pinfunction "6_6") (pintype "passive"))
      (node (ref "U1") (pin "21") (pinfunction "PF1(XTAL32K2)_21") (pintype "bidirectional"))
    )
    (net (code "11") (name "/LED2") (class "Default")
      (node (ref "J3") (pin "7") (pinfunction "7_7") (pintype "passive"))
      (node (ref "U1") (pin "22") (pinfunction "PF2_22") (pintype "bidirectional"))
    )
    (net (code "12") (name "/LED3") (class "Default")
      (node (ref "J3") (pin "8") (pinfunction "8_8") (pintype "passive"))
      (node (ref "U1") (pin "23") (pinfunction "PF3_23") (pintype "bidirectional"))
    )
    (net (code "13") (name "/MCU1 RX-TX MCU2") (class "Default")
      (node (ref "IC1") (pin "1") (pinfunction "PA5_1") (pintype "passive"))
    )
    (net (code "14") (name "/MCU1 TX-RX MCU2") (class "Default")
      (node (ref "IC1") (pin "48") (pinfunction "PA4_48") (pintype "passive+no_connect"))
    )
    (net (code "15") (name "/Motor_Current_sensor") (class "Default")
      (node (ref "C10") (pin "1") (pinfunction "1_1") (pintype "passive"))
      (node (ref "IC1") (pin "22") (pinfunction "PD2_22") (pintype "passive"))
      (node (ref "R6") (pin "2") (pinfunction "2_2") (pintype "passive"))
      (node (ref "U3") (pin "4") (pinfunction "OUT_4") (pintype "output"))
    )
    (net (code "16") (name "/Motor_brake") (class "Default")
      (node (ref "IC1") (pin "30") (pinfunction "PE0_30") (pintype "passive"))
      (node (ref "U4") (pin "2") (pinfunction "IN2_2") (pintype "input"))
    )
    (net (code "17") (name "/Motor_ut_neg") (class "Default")
      (node (ref "J1") (pin "2") (pinfunction "2_2") (pintype "passive"))
      (node (ref "U4") (pin "8") (pinfunction "OUT2_8") (pintype "power_in"))
    )
    (net (code "18") (name "/Motor_ut_pos") (class "Default")
      (node (ref "J1") (pin "1") (pinfunction "1_1") (pintype "passive"))
      (node (ref "U2") (pin "3") (pinfunction "IP-_3") (pintype "passive"))
      (node (ref "U2") (pin "4") (pinfunction "IP-_4") (pintype "passive"))
    )
    (net (code "19") (name "/Motor_voltage_sensor") (class "Default")
      (node (ref "D1") (pin "1") (pinfunction "K1_1") (pintype "passive"))
      (node (ref "D1") (pin "2") (pinfunction "K2_2") (pintype "passive"))
      (node (ref "IC1") (pin "21") (pinfunction "PD1_21") (pintype "passive"))
      (node (ref "R1") (pin "2") (pinfunction "2_2") (pintype "passive"))
    )
    (net (code "20") (name "/Motordriver_pos") (class "Default")
      (node (ref "R3") (pin "1") (pinfunction "1_1") (pintype "passive"))
      (node (ref "U2") (pin "1") (pinfunction "IP+_1") (pintype "passive"))
      (node (ref "U2") (pin "2") (pinfunction "IP+_2") (pintype "passive"))
      (node (ref "U4") (pin "6") (pinfunction "OUT1_6") (pintype "power_in"))
    )
    (net (code "21") (name "/Opto_Generator") (class "Default")
      (node (ref "IC1") (pin "8") (pinfunction "PB4_8") (pintype "passive"))
      (node (ref "R18") (pin "2") (pinfunction "2_2") (pintype "passive"))
    )
    (net (code "22") (name "/Opto_Motor") (class "Default")
      (node (ref "IC1") (pin "9") (pinfunction "PB5_9") (pintype "passive"))
      (node (ref "R22") (pin "2") (pinfunction "2_2") (pintype "passive"))
    )
    (net (code "23") (name "/PWM_motor") (class "Default")
      (node (ref "IC1") (pin "46") (pinfunction "PA2_46") (pintype "passive"))
      (node (ref "U4") (pin "3") (pinfunction "IN1_3") (pintype "input"))
    )
    (net (code "24") (name "/Potmeter") (class "Default")
      (node (ref "D9") (pin "1") (pinfunction "K1_1") (pintype "passive"))
      (node (ref "D9") (pin "2") (pinfunction "K2_2") (pintype "passive"))
      (node (ref "J3") (pin "9") (pinfunction "9_9") (pintype "passive"))
      (node (ref "U1") (pin "11") (pinfunction "PD1_11") (pintype "bidirectional"))
    )
    (net (code "25") (name "/SCL") (class "Default")
      (node (ref "P3") (pin "2") (pinfunction "2_2") (pintype "passive"))
      (node (ref "U1") (pin "9") (pinfunction "PC3_9") (pintype "bidirectional"))
    )
    (net (code "26") (name "/SDA") (class "Default")
      (node (ref "P3") (pin "1") (pinfunction "1_1") (pintype "passive"))
      (node (ref "U1") (pin "8") (pinfunction "PC2_8") (pintype "bidirectional"))
    )
    (net (code "27") (name "/SW1") (class "Default")
      (node (ref "J3") (pin "2") (pinfunction "2_2") (pintype "passive"))
      (node (ref "U1") (pin "15") (pinfunction "PD5_15") (pintype "bidirectional"))
    )
    (net (code "28") (name "/SW2") (class "Default")
      (node (ref "J3") (pin "3") (pinfunction "3_3") (pintype "passive"))
      (node (ref "U1") (pin "16") (pinfunction "PD6_16") (pintype "bidirectional"))
    )
    (net (code "29") (name "/SW3") (class "Default")
      (node (ref "J3") (pin "4") (pinfunction "4_4") (pintype "passive"))
      (node (ref "U1") (pin "17") (pinfunction "PD7_17") (pintype "bidirectional"))
    )
    (net (code "30") (name "/UPDI_32") (class "Default")
      (node (ref "P4") (pin "2") (pinfunction "2_2") (pintype "passive"))
      (node (ref "U1") (pin "27") (pinfunction "UPDI_27") (pintype "passive"))
    )
    (net (code "31") (name "/UPDI_48") (class "Default")
      (node (ref "IC1") (pin "41") (pinfunction "UPDI_41") (pintype "passive"))
      (node (ref "P5") (pin "2") (pinfunction "2_2") (pintype "passive"))
    )
    (net (code "32") (name "/USART RX") (class "Default")
      (node (ref "IC1") (pin "4") (pinfunction "PB0_4") (pintype "passive"))
      (node (ref "P2") (pin "2") (pinfunction "2_2") (pintype "passive"))
    )
    (net (code "33") (name "/USART TX") (class "Default")
      (node (ref "IC1") (pin "5") (pinfunction "PB1_5") (pintype "passive"))
      (node (ref "P2") (pin "1") (pinfunction "1_1") (pintype "passive"))
    )
    (net (code "34") (name "/USART0 RX") (class "Default")
      (node (ref "P1") (pin "2") (pinfunction "2_2") (pintype "passive"))
      (node (ref "U1") (pin "31") (pinfunction "PA1(XTALHF2)_31") (pintype "bidirectional"))
    )
    (net (code "35") (name "/USART0 TX") (class "Default")
      (node (ref "P1") (pin "1") (pinfunction "1_1") (pintype "passive"))
      (node (ref "U1") (pin "30") (pinfunction "PA0(XTALHF1)_30") (pintype "bidirectional"))
    )
    (net (code "36") (name "/XTALHFIN") (class "Default")
      (node (ref "C27") (pin "1") (pinfunction "1_1") (pintype "passive"))
      (node (ref "IC1") (pin "44") (pinfunction "PA0(XTALHF1)_44") (pintype "passive"))
      (node (ref "Y1") (pin "1") (pinfunction "1_1") (pintype "passive"))
    )
    (net (code "37") (name "/XTALHFOUT") (class "Default")
      (node (ref "C29") (pin "1") (pinfunction "1_1") (pintype "passive"))
      (node (ref "IC1") (pin "45") (pinfunction "PA1(XTALHF2)_45") (pintype "passive"))
      (node (ref "Y1") (pin "2") (pinfunction "2_2") (pintype "passive"))
    )
    (net (code "38") (name "3V3") (class "Default")
      (node (ref "C1") (pin "1") (pinfunction "1_1") (pintype "passive"))
      (node (ref "C11") (pin "1") (pinfunction "1_1") (pintype "passive"))
      (node (ref "C12") (pin "2") (pinfunction "2_2") (pintype "passive"))
      (node (ref "C16") (pin "1") (pinfunction "1_1") (pintype "passive"))
      (node (ref "C19") (pin "1") (pinfunction "1_1") (pintype "passive"))
      (node (ref "C2") (pin "2") (pinfunction "2_2") (pintype "passive"))
      (node (ref "C20") (pin "2") (pinfunction "2_2") (pintype "passive"))
      (node (ref "C21") (pin "2") (pinfunction "2_2") (pintype "passive"))
      (node (ref "C22") (pin "1") (pinfunction "1_1") (pintype "passive"))
      (node (ref "C25") (pin "1") (pinfunction "1_1") (pintype "passive"))
      (node (ref "C26") (pin "2") (pinfunction "2_2") (pintype "passive"))
      (node (ref "C3") (pin "1") (pinfunction "1_1") (pintype "passive"))
      (node (ref "C4") (pin "2") (pinfunction "2_2") (pintype "passive"))
      (node (ref "C6") (pin "1") (pinfunction "1_1") (pintype "passive"))
      (node (ref "C7") (pin "2") (pinfunction "2_2") (pintype "passive"))
      (node (ref "D7") (pin "2") (pinfunction "A_2") (pintype "passive"))
      (node (ref "IC1") (pin "14") (pinfunction "VDDIO2_14") (pintype "passive"))
      (node (ref "IC1") (pin "28") (pinfunction "AVDD_28") (pintype "passive"))
      (node (ref "IC1") (pin "42") (pinfunction "VDD_42") (pintype "passive"))
      (node (ref "J3") (pin "10") (pinfunction "10_10") (pintype "passive"))
      (node (ref "P4") (pin "4") (pinfunction "4_4") (pintype "passive"))
      (node (ref "P5") (pin "4") (pinfunction "4_4") (pintype "passive"))
      (node (ref "U1") (pin "10") (pinfunction "VDDIO2_10") (pintype "power_in"))
      (node (ref "U1") (pin "18") (pinfunction "AVDD_18") (pintype "power_in"))
      (node (ref "U1") (pin "28") (pinfunction "VDD_28") (pintype "power_in"))
      (node (ref "U5") (pin "2") (pinfunction "OUT_2") (pintype "power_in"))
      (node (ref "U5") (pin "4") (pinfunction "OUT_4") (pintype "power_in"))
    )
    (net (code "39") (name "5V") (class "Default")
      (node (ref "C15") (pin "1") (pinfunction "1_1") (pintype "passive"))
      (node (ref "C28") (pin "2") (pinfunction "2_2") (pintype "passive"))
      (node (ref "D4") (pin "2") (pinfunction "A_2") (pintype "passive"))
      (node (ref "P3") (pin "4") (pinfunction "4_4") (pintype "passive"))
      (node (ref "P8") (pin "3") (pinfunction "3_3") (pintype "passive"))
      (node (ref "P9") (pin "3") (pinfunction "3_3") (pintype "passive"))
      (node (ref "R19") (pin "2") (pinfunction "2_2") (pintype "passive"))
      (node (ref "R2") (pin "2") (pinfunction "2_2") (pintype "passive"))
      (node (ref "U2") (pin "8") (pinfunction "VCC_8") (pintype "power_in"))
      (node (ref "U3") (pin "5") (pinfunction "V+_5") (pintype "power_in"))
      (node (ref "U6") (pin "4") (pinfunction "OUT_4") (pintype "power_in"))
      (node (ref "U8") (pin "5") (pinfunction "V+_5") (pintype "power_in"))
      (node (ref "U9") (pin "8") (pinfunction "VCC_8") (pintype "power_in"))
    )
    (net (code "40") (name "12V") (class "Default")
      (node (ref "C18") (pin "2") (pinfunction "A_2") (pintype "passive"))
      (node (ref "C23") (pin "1") (pinfunction "1_1") (pintype "passive"))
      (node (ref "C5") (pin "2") (pinfunction "A_2") (pintype "passive"))
      (node (ref "C8") (pin "1") (pinfunction "1_1") (pintype "passive"))
      (node (ref "D2") (pin "2") (pinfunction "A_2") (pintype "passive"))
      (node (ref "PS1") (pin "3") (pinfunction "+VO_3") (pintype "passive"))
      (node (ref "U4") (pin "5") (pinfunction "VM_5") (pintype "power_in"))
      (node (ref "U7") (pin "5") (pinfunction "V+_5") (pintype "power_in"))
    )
    (net (code "41") (name "24V") (class "Default")
      (node (ref "C13") (pin "2") (pinfunction "A_2") (pintype "passive"))
      (node (ref "C14") (pin "2") (pinfunction "A_2") (pintype "passive"))
      (node (ref "C17") (pin "2") (pinfunction "A_2") (pintype "passive"))
      (node (ref "D3") (pin "2") (pinfunction "K_2") (pintype "passive"))
      (node (ref "PS1") (pin "1") (pinfunction "+VIN_1") (pintype "passive"))
      (node (ref "U5") (pin "3") (pinfunction "IN_3") (pintype "power_in"))
      (node (ref "U6") (pin "3") (pinfunction "IN_3") (pintype "power_in"))
    )
    (net (code "42") (name "GND") (class "Default")
      (node (ref "C1") (pin "2") (pinfunction "2_2") (pintype "passive"))
      (node (ref "C11") (pin "2") (pinfunction "2_2") (pintype "passive"))
      (node (ref "C12") (pin "1") (pinfunction "1_1") (pintype "passive"))
      (node (ref "C13") (pin "1") (pinfunction "C_1") (pintype "passive"))
      (node (ref "C14") (pin "1") (pinfunction "C_1") (pintype "passive"))
      (node (ref "C15") (pin "2") (pinfunction "2_2") (pintype "passive"))
      (node (ref "C16") (pin "2") (pinfunction "2_2") (pintype "passive"))
      (node (ref "C17") (pin "1") (pinfunction "C_1") (pintype "passive"))
      (node (ref "C18") (pin "1") (pinfunction "C_1") (pintype "passive"))
      (node (ref "C19") (pin "2") (pinfunction "2_2") (pintype "passive"))
      (node (ref "C2") (pin "1") (pinfunction "1_1") (pintype "passive"))
      (node (ref "C20") (pin "1") (pinfunction "1_1") (pintype "passive"))
      (node (ref "C21") (pin "1") (pinfunction "1_1") (pintype "passive"))
      (node (ref "C22") (pin "2") (pinfunction "2_2") (pintype "passive"))
      (node (ref "C23") (pin "2") (pinfunction "2_2") (pintype "passive"))
      (node (ref "C24") (pin "1") (pinfunction "1_1") (pintype "passive"))
      (node (ref "C25") (pin "2") (pinfunction "2_2") (pintype "passive"))
      (node (ref "C26") (pin "1") (pinfunction "1_1") (pintype "passive"))
      (node (ref "C27") (pin "2") (pinfunction "2_2") (pintype "passive"))
      (node (ref "C28") (pin "1") (pinfunction "1_1") (pintype "passive"))
      (node (ref "C29") (pin "2") (pinfunction "2_2") (pintype "passive"))
      (node (ref "C3") (pin "2") (pinfunction "2_2") (pintype "passive"))
      (node (ref "C30") (pin "2") (pinfunction "2_2") (pintype "passive"))
      (node (ref "C4") (pin "1") (pinfunction "1_1") (pintype "passive"))
      (node (ref "C5") (pin "1") (pinfunction "C_1") (pintype "passive"))
      (node (ref "C6") (pin "2") (pinfunction "2_2") (pintype "passive"))
      (node (ref "C7") (pin "1") (pinfunction "1_1") (pintype "passive"))
      (node (ref "C8") (pin "2") (pinfunction "2_2") (pintype "passive"))
      (node (ref "C9") (pin "2") (pinfunction "2_2") (pintype "passive"))
      (node (ref "D1") (pin "3") (pinfunction "A_3") (pintype "passive"))
      (node (ref "D5") (pin "1") (pinfunction "A_1") (pintype "passive"))
      (node (ref "D6") (pin "3") (pinfunction "A_3") (pintype "passive"))
      (node (ref "D8") (pin "3") (pinfunction "A_3") (pintype "passive"))
      (node (ref "IC1") (pin "15") (pinfunction "GND_1_15") (pintype "passive"))
      (node (ref "IC1") (pin "29") (pinfunction "GND_2_29") (pintype "passive"))
      (node (ref "IC1") (pin "43") (pinfunction "GND_3_43") (pintype "passive"))
      (node (ref "J3") (pin "1") (pinfunction "1_1") (pintype "passive"))
      (node (ref "J3") (pin "MP1") (pinfunction "MP1_MP1") (pintype "passive"))
      (node (ref "J3") (pin "MP2") (pinfunction "MP2_MP2") (pintype "passive"))
      (node (ref "J4") (pin "2") (pinfunction "2_2") (pintype "passive"))
      (node (ref "P1") (pin "3") (pinfunction "3_3") (pintype "passive"))
      (node (ref "P2") (pin "3") (pinfunction "3_3") (pintype "passive"))
      (node (ref "P3") (pin "3") (pinfunction "3_3") (pintype "passive"))
      (node (ref "P4") (pin "3") (pinfunction "3_3") (pintype "passive"))
      (node (ref "P5") (pin "3") (pinfunction "3_3") (pintype "passive"))
      (node (ref "P6") (pin "2") (pinfunction "2_2") (pintype "passive"))
      (node (ref "P7") (pin "1") (pinfunction "1_1") (pintype "passive"))
      (node (ref "P8") (pin "1") (pinfunction "1_1") (pintype "passive"))
      (node (ref "P9") (pin "1") (pinfunction "1_1") (pintype "passive"))
      (node (ref "PS1") (pin "2") (pinfunction "GND_2") (pintype "passive"))
      (node (ref "Q2") (pin "2") (pinfunction "S_2") (pintype "passive"))
      (node (ref "R1") (pin "3") (pinfunction "3_3") (pintype "passive"))
      (node (ref "R10") (pin "2") (pinfunction "2_2") (pintype "passive"))
      (node (ref "R12") (pin "2") (pinfunction "2_2") (pintype "passive"))
      (node (ref "R13") (pin "3") (pinfunction "3_3") (pintype "passive"))
      (node (ref "R14") (pin "1") (pinfunction "1_1") (pintype "passive"))
      (node (ref "R15") (pin "2") (pinfunction "2_2") (pintype "passive"))
      (node (ref "R17") (pin "3") (pinfunction "3_3") (pintype "passive"))
      (node (ref "R18") (pin "1") (pinfunction "1_1") (pintype "passive"))
      (node (ref "R21") (pin "1") (pinfunction "1_1") (pintype "passive"))
      (node (ref "R22") (pin "1") (pinfunction "1_1") (pintype "passive"))
      (node (ref "R23") (pin "1") (pinfunction "1_1") (pintype "passive"))
      (node (ref "R4") (pin "1") (pinfunction "1_1") (pintype "passive"))
      (node (ref "R7") (pin "2") (pinfunction "2_2") (pintype "passive"))
      (node (ref "U1") (pin "19") (pinfunction "GND_19") (pintype "power_in"))
      (node (ref "U1") (pin "29") (pinfunction "GND_29") (pintype "power_in"))
      (node (ref "U2") (pin "5") (pinfunction "GND_5") (pintype "power_in"))
      (node (ref "U3") (pin "2") (pinfunction "V-_2") (pintype "power_in"))
      (node (ref "U4") (pin "1") (pinfunction "GND_1") (pintype "power_in"))
      (node (ref "U4") (pin "7") (pinfunction "PGND_7") (pintype "power_in"))
      (node (ref "U4") (pin "9") (pinfunction "Thermal_Pad_9") (pintype "power_in"))
      (node (ref "U5") (pin "1") (pinfunction "GND_1") (pintype "power_in"))
      (node (ref "U6") (pin "1") (pinfunction "GND_1") (pintype "power_in"))
      (node (ref "U7") (pin "2") (pinfunction "V-_2") (pintype "power_in"))
      (node (ref "U8") (pin "2") (pinfunction "V-_2") (pintype "power_in"))
      (node (ref "U9") (pin "5") (pinfunction "GND_5") (pintype "power_in"))
    )
    (net (code "43") (name "Net-(D2-K)") (class "Default")
      (node (ref "D2") (pin "1") (pinfunction "K_1") (pintype "passive"))
      (node (ref "R10") (pin "1") (pinfunction "1_1") (pintype "passive"))
    )
    (net (code "44") (name "Net-(D3-A)") (class "Default")
      (node (ref "D3") (pin "1") (pinfunction "A_1") (pintype "passive"))
      (node (ref "J2") (pin "1") (pinfunction "1_1") (pintype "passive"))
    )
    (net (code "45") (name "Net-(D4-K)") (class "Default")
      (node (ref "D4") (pin "1") (pinfunction "K_1") (pintype "passive"))
      (node (ref "R12") (pin "1") (pinfunction "1_1") (pintype "passive"))
    )
    (net (code "46") (name "Net-(D5-K)") (class "Default")
      (node (ref "D5") (pin "2") (pinfunction "K_2") (pintype "passive"))
      (node (ref "J2") (pin "2") (pinfunction "2_2") (pintype "passive"))
    )
    (net (code "47") (name "Net-(D6-K1)") (class "Default")
      (node (ref "C24") (pin "2") (pinfunction "2_2") (pintype "passive"))
      (node (ref "D6") (pin "1") (pinfunction "K1_1") (pintype "passive"))
      (node (ref "D6") (pin "2") (pinfunction "K2_2") (pintype "passive"))
      (node (ref "R8") (pin "2") (pinfunction "2_2") (pintype "passive"))
      (node (ref "R9") (pin "2") (pinfunction "2_2") (pintype "passive"))
    )
    (net (code "48") (name "Net-(D7-K)") (class "Default")
      (node (ref "D7") (pin "1") (pinfunction "K_1") (pintype "passive"))
      (node (ref "R15") (pin "1") (pinfunction "1_1") (pintype "passive"))
    )
    (net (code "49") (name "Net-(J4-Pad1)") (class "Default")
      (node (ref "J4") (pin "1") (pinfunction "1_1") (pintype "passive"))
      (node (ref "U9") (pin "3") (pinfunction "IP-_3") (pintype "passive"))
      (node (ref "U9") (pin "4") (pinfunction "IP-_4") (pintype "passive"))
    )
    (net (code "50") (name "Net-(P7-Pad2)") (class "Default")
      (node (ref "P7") (pin "2") (pinfunction "2_2") (pintype "passive"))
      (node (ref "R8") (pin "1") (pinfunction "1_1") (pintype "passive"))
    )
    (net (code "51") (name "Net-(P8-Pad2)") (class "Default")
      (node (ref "P8") (pin "2") (pinfunction "2_2") (pintype "passive"))
      (node (ref "R18") (pin "3") (pinfunction "3_3") (pintype "passive"))
    )
    (net (code "52") (name "Net-(P9-Pad2)") (class "Default")
      (node (ref "P9") (pin "2") (pinfunction "2_2") (pintype "passive"))
      (node (ref "R22") (pin "3") (pinfunction "3_3") (pintype "passive"))
    )
    (net (code "53") (name "Net-(Q1-GATE)") (class "Default")
      (node (ref "Q1") (pin "1") (pinfunction "GATE_1") (pintype "passive"))
      (node (ref "Q2") (pin "3") (pinfunction "D_3") (pintype "passive"))
      (node (ref "R20") (pin "1") (pinfunction "1_1") (pintype "passive"))
    )
    (net (code "54") (name "Net-(Q1-SOURCE)") (class "Default")
      (node (ref "Q1") (pin "3") (pinfunction "SOURCE_3") (pintype "passive"))
      (node (ref "R23") (pin "2") (pinfunction "2_2") (pintype "passive"))
    )
    (net (code "55") (name "Net-(R1-Pad1)") (class "Default")
      (node (ref "R1") (pin "1") (pinfunction "1_1") (pintype "passive"))
      (node (ref "R3") (pin "2") (pinfunction "2_2") (pintype "passive"))
    )
    (net (code "56") (name "Net-(R11-Pad2)") (class "Default")
      (node (ref "R11") (pin "2") (pinfunction "2_2") (pintype "passive"))
      (node (ref "R14") (pin "2") (pinfunction "2_2") (pintype "passive"))
    )
    (net (code "57") (name "Net-(R16-Pad1)") (class "Default")
      (node (ref "R16") (pin "1") (pinfunction "1_1") (pintype "passive"))
      (node (ref "R17") (pin "1") (pinfunction "1_1") (pintype "passive"))
    )
    (net (code "58") (name "Net-(U2-FILTER)") (class "Default")
      (node (ref "C9") (pin "1") (pinfunction "1_1") (pintype "passive"))
      (node (ref "U2") (pin "6") (pinfunction "FILTER_6") (pintype "passive"))
    )
    (net (code "59") (name "Net-(U2-VIOUT)") (class "Default")
      (node (ref "R5") (pin "1") (pinfunction "1_1") (pintype "passive"))
      (node (ref "U2") (pin "7") (pinfunction "VIOUT_7") (pintype "passive"))
    )
    (net (code "60") (name "Net-(U3-IN+)") (class "Default")
      (node (ref "R2") (pin "1") (pinfunction "1_1") (pintype "passive"))
      (node (ref "R4") (pin "2") (pinfunction "2_2") (pintype "passive"))
      (node (ref "U3") (pin "1") (pinfunction "IN+_1") (pintype "tri_state"))
    )
    (net (code "61") (name "Net-(U3-IN-)") (class "Default")
      (node (ref "C10") (pin "2") (pinfunction "2_2") (pintype "passive"))
      (node (ref "R5") (pin "2") (pinfunction "2_2") (pintype "passive"))
      (node (ref "R6") (pin "1") (pinfunction "1_1") (pintype "passive"))
      (node (ref "U3") (pin "3") (pinfunction "IN-_3") (pintype "tri_state"))
    )
    (net (code "62") (name "Net-(U4-ILIM)") (class "Default")
      (node (ref "R7") (pin "1") (pinfunction "1_1") (pintype "passive"))
      (node (ref "U4") (pin "4") (pinfunction "ILIM_4") (pintype "passive"))
    )
    (net (code "63") (name "Net-(U7-IN-)") (class "Default")
      (node (ref "R13") (pin "2") (pinfunction "2_2") (pintype "passive"))
      (node (ref "U7") (pin "3") (pinfunction "IN-_3") (pintype "tri_state"))
    )
    (net (code "64") (name "Net-(U7-OUT)") (class "Default")
      (node (ref "P6") (pin "1") (pinfunction "1_1") (pintype "passive"))
      (node (ref "R13") (pin "1") (pinfunction "1_1") (pintype "passive"))
      (node (ref "U7") (pin "4") (pinfunction "OUT_4") (pintype "passive"))
    )
    (net (code "65") (name "Net-(U8-IN+)") (class "Default")
      (node (ref "R19") (pin "1") (pinfunction "1_1") (pintype "passive"))
      (node (ref "R21") (pin "2") (pinfunction "2_2") (pintype "passive"))
      (node (ref "U8") (pin "1") (pinfunction "IN+_1") (pintype "tri_state"))
    )
    (net (code "66") (name "Net-(U8-IN-)") (class "Default")
      (node (ref "C31") (pin "2") (pinfunction "2_2") (pintype "passive"))
      (node (ref "R24") (pin "2") (pinfunction "2_2") (pintype "passive"))
      (node (ref "R25") (pin "1") (pinfunction "1_1") (pintype "passive"))
      (node (ref "U8") (pin "3") (pinfunction "IN-_3") (pintype "tri_state"))
    )
    (net (code "67") (name "Net-(U9-FILTER)") (class "Default")
      (node (ref "C30") (pin "1") (pinfunction "1_1") (pintype "passive"))
      (node (ref "U9") (pin "6") (pinfunction "FILTER_6") (pintype "passive"))
    )
    (net (code "68") (name "Net-(U9-VIOUT)") (class "Default")
      (node (ref "R24") (pin "1") (pinfunction "1_1") (pintype "passive"))
      (node (ref "U9") (pin "7") (pinfunction "VIOUT_7") (pintype "passive"))
    )
    (net (code "69") (name "unconnected-(D9-A-Pad3)") (class "Default")
      (node (ref "D9") (pin "3") (pinfunction "A_3") (pintype "passive"))
    )
    (net (code "70") (name "unconnected-(IC1-PA3-Pad47)") (class "Default")
      (node (ref "IC1") (pin "47") (pinfunction "PA3_47") (pintype "passive"))
    )
    (net (code "71") (name "unconnected-(IC1-PA6-Pad2)") (class "Default")
      (node (ref "IC1") (pin "2") (pinfunction "PA6_2") (pintype "passive"))
    )
    (net (code "72") (name "unconnected-(IC1-PA7-Pad3)") (class "Default")
      (node (ref "IC1") (pin "3") (pinfunction "PA7_3") (pintype "passive"))
    )
    (net (code "73") (name "unconnected-(IC1-PB2-Pad6)") (class "Default")
      (node (ref "IC1") (pin "6") (pinfunction "PB2_6") (pintype "passive"))
    )
    (net (code "74") (name "unconnected-(IC1-PB3-Pad7)") (class "Default")
      (node (ref "IC1") (pin "7") (pinfunction "PB3_7") (pintype "passive"))
    )
    (net (code "75") (name "unconnected-(IC1-PC0-Pad10)") (class "Default")
      (node (ref "IC1") (pin "10") (pinfunction "PC0_10") (pintype "passive"))
    )
    (net (code "76") (name "unconnected-(IC1-PC1-Pad11)") (class "Default")
      (node (ref "IC1") (pin "11") (pinfunction "PC1_11") (pintype "passive"))
    )
    (net (code "77") (name "unconnected-(IC1-PC2-Pad12)") (class "Default")
      (node (ref "IC1") (pin "12") (pinfunction "PC2_12") (pintype "passive"))
    )
    (net (code "78") (name "unconnected-(IC1-PC3-Pad13)") (class "Default")
      (node (ref "IC1") (pin "13") (pinfunction "PC3_13") (pintype "passive"))
    )
    (net (code "79") (name "unconnected-(IC1-PC4-Pad16)") (class "Default")
      (node (ref "IC1") (pin "16") (pinfunction "PC4_16") (pintype "passive"))
    )
    (net (code "80") (name "unconnected-(IC1-PC5-Pad17)") (class "Default")
      (node (ref "IC1") (pin "17") (pinfunction "PC5_17") (pintype "passive"))
    )
    (net (code "81") (name "unconnected-(IC1-PC6-Pad18)") (class "Default")
      (node (ref "IC1") (pin "18") (pinfunction "PC6_18") (pintype "passive"))
    )
    (net (code "82") (name "unconnected-(IC1-PC7-Pad19)") (class "Default")
      (node (ref "IC1") (pin "19") (pinfunction "PC7_19") (pintype "passive"))
    )
    (net (code "83") (name "unconnected-(IC1-PD6-Pad26)") (class "Default")
      (node (ref "IC1") (pin "26") (pinfunction "PD6_26") (pintype "passive"))
    )
    (net (code "84") (name "unconnected-(IC1-PD7-Pad27)") (class "Default")
      (node (ref "IC1") (pin "27") (pinfunction "PD7_27") (pintype "passive"))
    )
    (net (code "85") (name "unconnected-(IC1-PE1-Pad31)") (class "Default")
      (node (ref "IC1") (pin "31") (pinfunction "PE1_31") (pintype "passive"))
    )
    (net (code "86") (name "unconnected-(IC1-PE2-Pad32)") (class "Default")
      (node (ref "IC1") (pin "32") (pinfunction "PE2_32") (pintype "passive"))
    )
    (net (code "87") (name "unconnected-(IC1-PE3-Pad33)") (class "Default")
      (node (ref "IC1") (pin "33") (pinfunction "PE3_33") (pintype "passive"))
    )
    (net (code "88") (name "unconnected-(IC1-PF0(XTAL32K1)-Pad34)") (class "Default")
      (node (ref "IC1") (pin "34") (pinfunction "PF0(XTAL32K1)_34") (pintype "passive"))
    )
    (net (code "89") (name "unconnected-(IC1-PF1(XTAL32K2)-Pad35)") (class "Default")
      (node (ref "IC1") (pin "35") (pinfunction "PF1(XTAL32K2)_35") (pintype "passive"))
    )
    (net (code "90") (name "unconnected-(IC1-PF2-Pad36)") (class "Default")
      (node (ref "IC1") (pin "36") (pinfunction "PF2_36") (pintype "passive"))
    )
    (net (code "91") (name "unconnected-(IC1-PF3-Pad37)") (class "Default")
      (node (ref "IC1") (pin "37") (pinfunction "PF3_37") (pintype "passive"))
    )
    (net (code "92") (name "unconnected-(IC1-PF4-Pad38)") (class "Default")
      (node (ref "IC1") (pin "38") (pinfunction "PF4_38") (pintype "passive"))
    )
    (net (code "93") (name "unconnected-(IC1-PF5-Pad39)") (class "Default")
      (node (ref "IC1") (pin "39") (pinfunction "PF5_39") (pintype "passive"))
    )
    (net (code "94") (name "unconnected-(MP1-MNT_1-Pad1)") (class "Default")
      (node (ref "MP1") (pin "1") (pinfunction "MNT_1_1") (pintype "passive"))
    )
    (net (code "95") (name "unconnected-(U1-PA3-Pad1)") (class "Default")
      (node (ref "U1") (pin "1") (pinfunction "PA3_1") (pintype "bidirectional"))
    )
    (net (code "96") (name "unconnected-(U1-PA4-Pad2)") (class "Default")
      (node (ref "U1") (pin "2") (pinfunction "PA4_2") (pintype "bidirectional"))
    )
    (net (code "97") (name "unconnected-(U1-PA5-Pad3)") (class "Default")
      (node (ref "U1") (pin "3") (pinfunction "PA5_3") (pintype "bidirectional"))
    )
    (net (code "98") (name "unconnected-(U1-PA6-Pad4)") (class "Default")
      (node (ref "U1") (pin "4") (pinfunction "PA6_4") (pintype "bidirectional"))
    )
    (net (code "99") (name "unconnected-(U1-PA7-Pad5)") (class "Default")
      (node (ref "U1") (pin "5") (pinfunction "PA7_5") (pintype "bidirectional"))
    )
    (net (code "100") (name "unconnected-(U1-PC0-Pad6)") (class "Default")
      (node (ref "U1") (pin "6") (pinfunction "PC0_6") (pintype "bidirectional"))
    )
    (net (code "101") (name "unconnected-(U1-PC1-Pad7)") (class "Default")
      (node (ref "U1") (pin "7") (pinfunction "PC1_7") (pintype "bidirectional"))
    )
    (net (code "102") (name "unconnected-(U1-PD2-Pad12)") (class "Default")
      (node (ref "U1") (pin "12") (pinfunction "PD2_12") (pintype "bidirectional"))
    )
    (net (code "103") (name "unconnected-(U1-PD3-Pad13)") (class "Default")
      (node (ref "U1") (pin "13") (pinfunction "PD3_13") (pintype "bidirectional"))
    )
    (net (code "104") (name "unconnected-(U1-PD4-Pad14)") (class "Default")
      (node (ref "U1") (pin "14") (pinfunction "PD4_14") (pintype "bidirectional"))
    )
    (net (code "105") (name "unconnected-(U1-PF4-Pad24)") (class "Default")
      (node (ref "U1") (pin "24") (pinfunction "PF4_24") (pintype "bidirectional"))
    )
    (net (code "106") (name "unconnected-(U1-PF5-Pad25)") (class "Default")
      (node (ref "U1") (pin "25") (pinfunction "PF5_25") (pintype "bidirectional"))
    )
  )
)
